# HF_AMP.net
KiCad netlist of a schematic drawn in Altium Designer
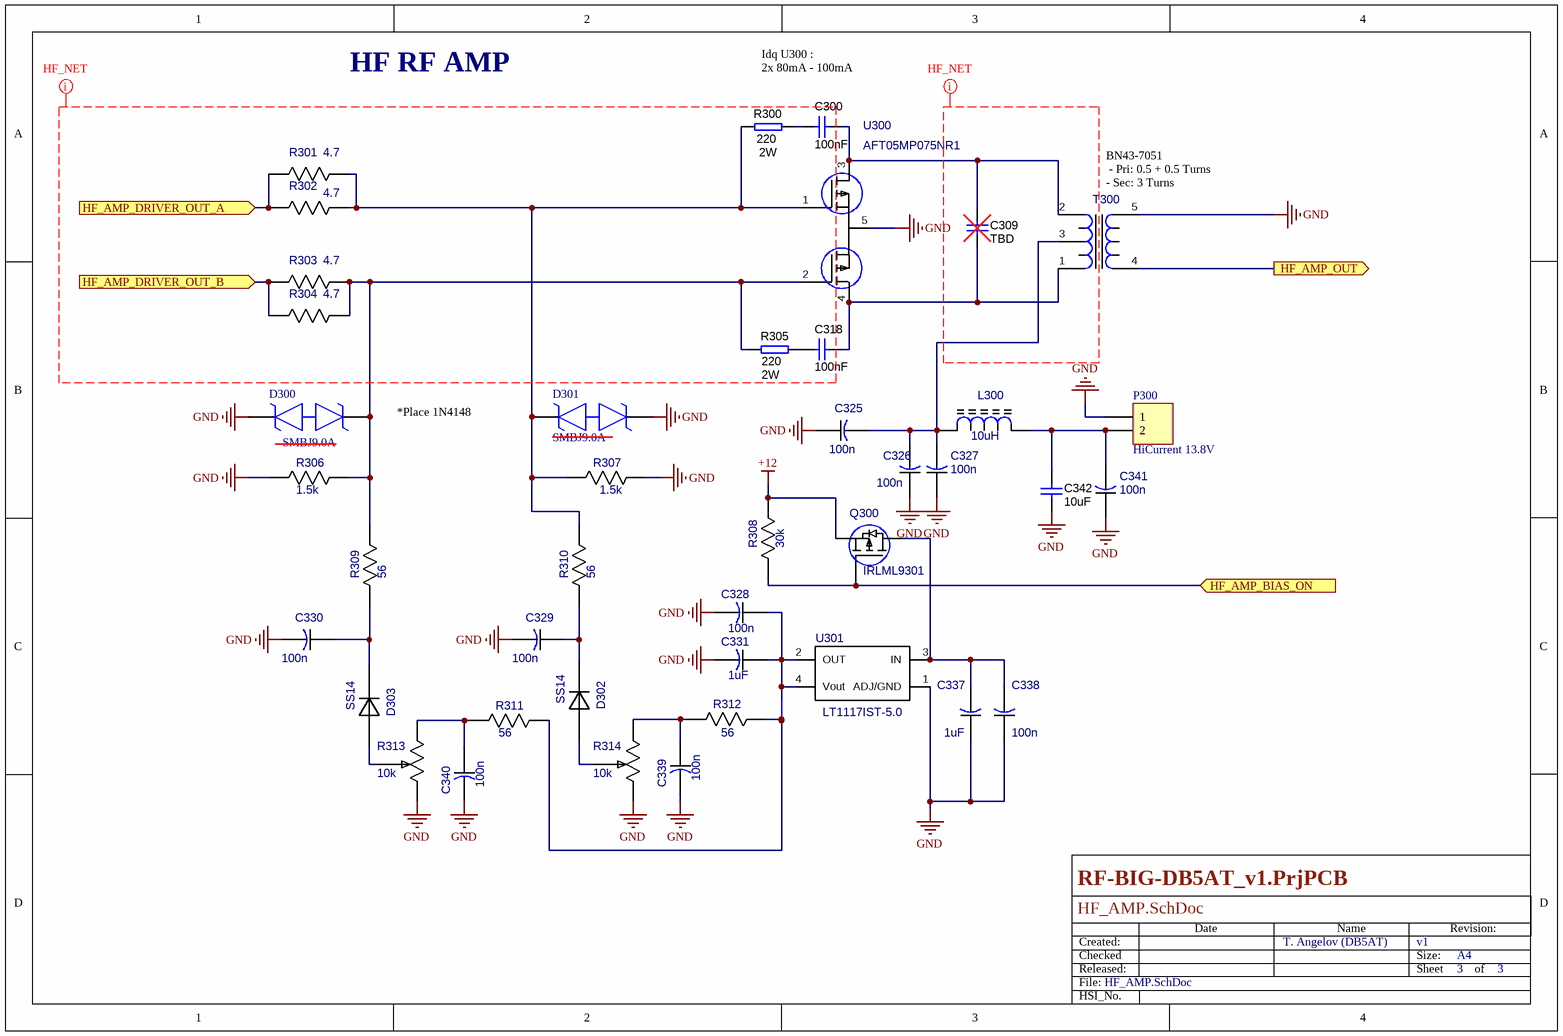
[diagram p0: HF_AMP.SchDoc]

(export (version "E")
  (design (tool "Eeschema 10.0.6"))
  (components
    (comp (ref "C300")
      (value "100nF")
      (footprint "1206_180")
      (description "CAP, CERM, +/- 10%, X7R, 1206")
      (libsource (lib "PSFB_v1") (part "C1206"))
    )
    (comp (ref "C309")
      (value "TBD")
      (footprint "1206_180")
      (description "CAP, CERM, +/- 10%, X7R, 1206")
      (libsource (lib "PSFB_v1") (part "C1206"))
    )
    (comp (ref "C318")
      (value "100nF")
      (footprint "1206_180")
      (description "CAP, CERM, +/- 10%, X7R, 1206")
      (libsource (lib "PSFB_v1") (part "C1206"))
    )
    (comp (ref "C325")
      (value "100n")
      (footprint "CAP_1206")
      (description "CAP_1206")
      (libsource (lib "*") (part "CAP_1206"))
    )
    (comp (ref "C326")
      (value "100n")
      (footprint "CAP_1206")
      (description "CAP_1206")
      (libsource (lib "*") (part "CAP_1206"))
    )
    (comp (ref "C327")
      (value "100n")
      (footprint "CAP_1206")
      (description "CAP_1206")
      (libsource (lib "*") (part "CAP_1206"))
    )
    (comp (ref "C328")
      (value "100n")
      (footprint "CAP_0805")
      (description "CAP_0805")
      (libsource (lib "*") (part "CAP_0805"))
    )
    (comp (ref "C329")
      (value "100n")
      (footprint "CAP_0805")
      (description "CAP_0805")
      (libsource (lib "*") (part "CAP_0805"))
    )
    (comp (ref "C330")
      (value "100n")
      (footprint "CAP_0805")
      (description "CAP_0805")
      (libsource (lib "*") (part "CAP_0805"))
    )
    (comp (ref "C331")
      (value "1uF")
      (footprint "CAP_0805")
      (description "CAP_0805")
      (libsource (lib "*") (part "CAP_0805"))
    )
    (comp (ref "C337")
      (value "1uF")
      (footprint "CAP_0805")
      (description "CAP_0805")
      (libsource (lib "*") (part "CAP_0805"))
    )
    (comp (ref "C338")
      (value "100n")
      (footprint "CAP_0805")
      (description "CAP_0805")
      (libsource (lib "*") (part "CAP_0805"))
    )
    (comp (ref "C339")
      (value "100n")
      (footprint "CAP_0805")
      (description "CAP_0805")
      (libsource (lib "*") (part "CAP_0805"))
    )
    (comp (ref "C340")
      (value "100n")
      (footprint "CAP_0805")
      (description "CAP_0805")
      (libsource (lib "*") (part "CAP_0805"))
    )
    (comp (ref "C341")
      (value "100n")
      (footprint "CAP_0805")
      (description "CAP_1206")
      (libsource (lib "*") (part "CAP_1206"))
    )
    (comp (ref "C342")
      (value "10uF")
      (footprint "1206_180")
      (description "CAP, CERM, +/- 10%, X7R, 1206")
      (libsource (lib "PSFB_v1") (part "C1206"))
    )
    (comp (ref "D300")
      (value "SMBJ9.0A")
      (footprint "SMBJ36CATR")
      (description "TVS Diode (Bi-directional)")
      (fields
        (field (name "MANUFACTURER_PART_NUMBER") "SMBJ16CA")
        (field (name "MOUSER PART NUMBER") "652-SMBJ16CA")
      )
      (libsource (lib "*") (part "SMBJ16CA"))
    )
    (comp (ref "D301")
      (value "SMBJ9.0A")
      (footprint "SMBJ36CATR")
      (description "TVS Diode (Bi-directional)")
      (fields
        (field (name "MANUFACTURER_PART_NUMBER") "SMBJ16CA")
        (field (name "MOUSER PART NUMBER") "652-SMBJ16CA")
      )
      (libsource (lib "*") (part "SMBJ16CA"))
    )
    (comp (ref "D302") (value "SS14") (footprint "SS14") (libsource (lib "*") (part "SS14")))
    (comp (ref "D303") (value "SS14") (footprint "SS14") (libsource (lib "*") (part "SS14")))
    (comp (ref "L300")
      (value "10uH")
      (footprint "IND_FERRITE_CORE")
      (description "Inductor")
      (libsource (lib "*") (part "IND_FERRITE_CORE"))
    )
    (comp (ref "P300")
      (value "HiCurrent 13.8V")
      (footprint "2 Pole Screw")
      (description "Header, 2-Pin")
      (fields (field (name "PUBLISHER") "Altium Limited"))
      (libsource (lib "Miscellaneous Connectors") (part "Header 2"))
    )
    (comp (ref "Q300")
      (value "IRLML9301")
      (footprint "SOT23")
      (description "MOSFET")
      (libsource (lib "*") (part "MOSFET_ENH_PD"))
    )
    (comp (ref "R300")
      (value "220")
      (footprint "Res_2W")
      (description "RES")
      (fields (field (name "VALUE2") "2W"))
      (libsource (lib "PSFB_v1") (part "R1206"))
    )
    (comp (ref "R301")
      (value "4.7")
      (footprint "RES_1206")
      (description "RES_1206")
      (libsource (lib "*") (part "RES_1206"))
    )
    (comp (ref "R302")
      (value "4.7")
      (footprint "RES_1206")
      (description "RES_1206")
      (libsource (lib "*") (part "RES_1206"))
    )
    (comp (ref "R303")
      (value "4.7")
      (footprint "RES_1206")
      (description "RES_1206")
      (libsource (lib "*") (part "RES_1206"))
    )
    (comp (ref "R304")
      (value "4.7")
      (footprint "RES_1206")
      (description "RES_1206")
      (libsource (lib "*") (part "RES_1206"))
    )
    (comp (ref "R305")
      (value "220")
      (footprint "Res_2W")
      (description "RES")
      (fields (field (name "VALUE2") "2W"))
      (libsource (lib "PSFB_v1") (part "R1206"))
    )
    (comp (ref "R306")
      (value "1.5k")
      (footprint "RES_0805")
      (description "RES_0805")
      (libsource (lib "*") (part "RES_0805"))
    )
    (comp (ref "R307")
      (value "1.5k")
      (footprint "RES_0805")
      (description "RES_0805")
      (libsource (lib "*") (part "RES_0805"))
    )
    (comp (ref "R308")
      (value "30k")
      (footprint "RES_0805")
      (description "RES_0805")
      (libsource (lib "*") (part "RES_0805"))
    )
    (comp (ref "R309")
      (value "56")
      (footprint "RES_0805")
      (description "RES_0805")
      (libsource (lib "*") (part "RES_0805"))
    )
    (comp (ref "R310")
      (value "56")
      (footprint "RES_0805")
      (description "RES_0805")
      (libsource (lib "*") (part "RES_0805"))
    )
    (comp (ref "R311")
      (value "56")
      (footprint "RES_0805")
      (description "RES_0805")
      (libsource (lib "*") (part "RES_0805"))
    )
    (comp (ref "R312")
      (value "56")
      (footprint "RES_0805")
      (description "RES_0805")
      (libsource (lib "*") (part "RES_0805"))
    )
    (comp (ref "R313")
      (value "10k")
      (footprint "3296W-1")
      (description "3296W-1-103LF")
      (fields (field (name "Comment") "ADJ-10k"))
      (libsource (lib "*") (part "306J"))
    )
    (comp (ref "R314")
      (value "10k")
      (footprint "3296W-1")
      (description "3296W-1-103LF")
      (fields (field (name "Comment") "ADJ-10k"))
      (libsource (lib "*") (part "306J"))
    )
    (comp (ref "T300")
      (value "TRANSF_HF2")
      (footprint "TRANSF_HF3 - bn43-7051")
      (libsource (lib "RF-UNIT-BIG") (part "TRANSF_RF2"))
    )
    (comp (ref "U300")
      (value "AFT05MP075NR1")
      (footprint "AFT05MP075NR1-Direct_Mount")
      (libsource (lib "RF-UNIT-BIG") (part "AFT05MP075NR1"))
    )
    (comp (ref "U301")
      (value "LT1117IST-5.0")
      (footprint "LT1117IST-ADJ")
      (libsource (lib "*") (part "LT1117IST-ADJ"))
    )
  )
  (nets
    (net (code "1") (name "+12") (class "Default")
      (node (ref "Q300") (pin "2") (pinfunction "S_2") (pintype "passive"))
      (node (ref "R308") (pin "2") (pinfunction "2_2") (pintype "passive"))
    )
    (net (code "2") (name "/HF_AMP_BIAS_ON") (class "Default")
      (node (ref "Q300") (pin "1") (pinfunction "G_1") (pintype "passive"))
      (node (ref "R308") (pin "1") (pinfunction "1_1") (pintype "passive"))
    )
    (net (code "3") (name "/HF_AMP_DRIVER_OUT_A") (class "Default")
      (node (ref "R301") (pin "1") (pinfunction "1_1") (pintype "passive"))
      (node (ref "R302") (pin "1") (pinfunction "1_1") (pintype "passive"))
    )
    (net (code "4") (name "/HF_AMP_DRIVER_OUT_B") (class "Default")
      (node (ref "R303") (pin "1") (pinfunction "1_1") (pintype "passive"))
      (node (ref "R304") (pin "1") (pinfunction "1_1") (pintype "passive"))
    )
    (net (code "5") (name "/HF_AMP_OUT") (class "Default")
      (node (ref "T300") (pin "4") (pinfunction "S1_4") (pintype "passive"))
    )
    (net (code "6") (name "GND") (class "Default")
      (node (ref "C325") (pin "1") (pinfunction "1_1") (pintype "passive"))
      (node (ref "C326") (pin "1") (pinfunction "1_1") (pintype "passive"))
      (node (ref "C327") (pin "1") (pinfunction "1_1") (pintype "passive"))
      (node (ref "C328") (pin "2") (pinfunction "2_2") (pintype "passive"))
      (node (ref "C329") (pin "2") (pinfunction "2_2") (pintype "passive"))
      (node (ref "C330") (pin "2") (pinfunction "2_2") (pintype "passive"))
      (node (ref "C331") (pin "2") (pinfunction "2_2") (pintype "passive"))
      (node (ref "C337") (pin "1") (pinfunction "1_1") (pintype "passive"))
      (node (ref "C338") (pin "1") (pinfunction "1_1") (pintype "passive"))
      (node (ref "C339") (pin "2") (pinfunction "2_2") (pintype "passive"))
      (node (ref "C340") (pin "2") (pinfunction "2_2") (pintype "passive"))
      (node (ref "C341") (pin "1") (pinfunction "1_1") (pintype "passive"))
      (node (ref "C342") (pin "1") (pinfunction "1_1") (pintype "passive"))
      (node (ref "D300") (pin "1") (pinfunction "1_1") (pintype "passive"))
      (node (ref "D301") (pin "1") (pinfunction "1_1") (pintype "passive"))
      (node (ref "P300") (pin "1") (pinfunction "1_1") (pintype "passive"))
      (node (ref "R306") (pin "1") (pinfunction "1_1") (pintype "passive"))
      (node (ref "R307") (pin "2") (pinfunction "2_2") (pintype "passive"))
      (node (ref "R313") (pin "1") (pinfunction "CCW_1") (pintype "passive"))
      (node (ref "R314") (pin "1") (pinfunction "CCW_1") (pintype "passive"))
      (node (ref "T300") (pin "5") (pinfunction "S2_5") (pintype "passive"))
      (node (ref "U300") (pin "5") (pinfunction "D1_5") (pintype "passive"))
      (node (ref "U301") (pin "1") (pinfunction "ADJ/GND_1") (pintype "passive"))
    )
    (net (code "7") (name "Net-(C300-Pad1)") (class "Default")
      (node (ref "C300") (pin "1") (pinfunction "1_1") (pintype "passive"))
      (node (ref "R300") (pin "2") (pinfunction "2_2") (pintype "passive"))
    )
    (net (code "8") (name "Net-(C318-Pad2)") (class "Default")
      (node (ref "C318") (pin "2") (pinfunction "2_2") (pintype "passive"))
      (node (ref "R305") (pin "1") (pinfunction "1_1") (pintype "passive"))
    )
    (net (code "9") (name "Net-(D302-A)") (class "Default")
      (node (ref "D302") (pin "2") (pinfunction "A_2") (pintype "passive"))
      (node (ref "R314") (pin "2") (pinfunction "W_2") (pintype "passive"))
    )
    (net (code "10") (name "Net-(D302-K)") (class "Default")
      (node (ref "C329") (pin "1") (pinfunction "1_1") (pintype "passive"))
      (node (ref "D302") (pin "1") (pinfunction "K_1") (pintype "passive"))
      (node (ref "R310") (pin "1") (pinfunction "1_1") (pintype "passive"))
    )
    (net (code "11") (name "Net-(D303-A)") (class "Default")
      (node (ref "D303") (pin "2") (pinfunction "A_2") (pintype "passive"))
      (node (ref "R313") (pin "2") (pinfunction "W_2") (pintype "passive"))
    )
    (net (code "12") (name "Net-(D303-K)") (class "Default")
      (node (ref "C330") (pin "1") (pinfunction "1_1") (pintype "passive"))
      (node (ref "D303") (pin "1") (pinfunction "K_1") (pintype "passive"))
      (node (ref "R309") (pin "1") (pinfunction "1_1") (pintype "passive"))
    )
    (net (code "13") (name "Net-(L300-A)") (class "Default")
      (node (ref "C325") (pin "2") (pinfunction "2_2") (pintype "passive"))
      (node (ref "C326") (pin "2") (pinfunction "2_2") (pintype "passive"))
      (node (ref "C327") (pin "2") (pinfunction "2_2") (pintype "passive"))
      (node (ref "L300") (pin "1") (pinfunction "A_1") (pintype "passive"))
      (node (ref "T300") (pin "3") (pinfunction "P3_3") (pintype "passive"))
    )
    (net (code "14") (name "Net-(L300-B)") (class "Default")
      (node (ref "C341") (pin "2") (pinfunction "2_2") (pintype "passive"))
      (node (ref "C342") (pin "2") (pinfunction "2_2") (pintype "passive"))
      (node (ref "L300") (pin "2") (pinfunction "B_2") (pintype "passive"))
      (node (ref "P300") (pin "2") (pinfunction "2_2") (pintype "passive"))
    )
    (net (code "15") (name "Net-(Q300-D)") (class "Default")
      (node (ref "C337") (pin "2") (pinfunction "2_2") (pintype "passive"))
      (node (ref "C338") (pin "2") (pinfunction "2_2") (pintype "passive"))
      (node (ref "Q300") (pin "3") (pinfunction "D_3") (pintype "passive"))
      (node (ref "U301") (pin "3") (pinfunction "IN_3") (pintype "passive"))
    )
    (net (code "16") (name "Net-(R313-CW)") (class "Default")
      (node (ref "C340") (pin "1") (pinfunction "1_1") (pintype "passive"))
      (node (ref "R311") (pin "1") (pinfunction "1_1") (pintype "passive"))
      (node (ref "R313") (pin "3") (pinfunction "CW_3") (pintype "passive"))
    )
    (net (code "17") (name "Net-(R314-CW)") (class "Default")
      (node (ref "C339") (pin "1") (pinfunction "1_1") (pintype "passive"))
      (node (ref "R312") (pin "1") (pinfunction "1_1") (pintype "passive"))
      (node (ref "R314") (pin "3") (pinfunction "CW_3") (pintype "passive"))
    )
    (net (code "18") (name "Net-(T300-P1)") (class "Default")
      (node (ref "C309") (pin "1") (pinfunction "1_1") (pintype "passive"))
      (node (ref "C318") (pin "1") (pinfunction "1_1") (pintype "passive"))
      (node (ref "T300") (pin "1") (pinfunction "P1_1") (pintype "passive"))
      (node (ref "U300") (pin "4") (pinfunction "D2_4") (pintype "passive"))
    )
    (net (code "19") (name "Net-(T300-P2)") (class "Default")
      (node (ref "C300") (pin "2") (pinfunction "2_2") (pintype "passive"))
      (node (ref "C309") (pin "2") (pinfunction "2_2") (pintype "passive"))
      (node (ref "T300") (pin "2") (pinfunction "P2_2") (pintype "passive"))
      (node (ref "U300") (pin "3") (pinfunction "D1_3") (pintype "passive"))
    )
    (net (code "20") (name "Net-(U300-G1)") (class "Default")
      (node (ref "D301") (pin "2") (pinfunction "2_2") (pintype "passive"))
      (node (ref "R300") (pin "1") (pinfunction "1_1") (pintype "passive"))
      (node (ref "R301") (pin "2") (pinfunction "2_2") (pintype "passive"))
      (node (ref "R302") (pin "2") (pinfunction "2_2") (pintype "passive"))
      (node (ref "R307") (pin "1") (pinfunction "1_1") (pintype "passive"))
      (node (ref "R310") (pin "2") (pinfunction "2_2") (pintype "passive"))
      (node (ref "U300") (pin "1") (pinfunction "G1_1") (pintype "passive"))
    )
    (net (code "21") (name "Net-(U300-G2)") (class "Default")
      (node (ref "D300") (pin "2") (pinfunction "2_2") (pintype "passive"))
      (node (ref "R303") (pin "2") (pinfunction "2_2") (pintype "passive"))
      (node (ref "R304") (pin "2") (pinfunction "2_2") (pintype "passive"))
      (node (ref "R305") (pin "2") (pinfunction "2_2") (pintype "passive"))
      (node (ref "R306") (pin "2") (pinfunction "2_2") (pintype "passive"))
      (node (ref "R309") (pin "2") (pinfunction "2_2") (pintype "passive"))
      (node (ref "U300") (pin "2") (pinfunction "G2_2") (pintype "passive"))
    )
    (net (code "22") (name "Net-(U301-OUT)") (class "Default")
      (node (ref "C328") (pin "1") (pinfunction "1_1") (pintype "passive"))
      (node (ref "C331") (pin "1") (pinfunction "1_1") (pintype "passive"))
      (node (ref "R311") (pin "2") (pinfunction "2_2") (pintype "passive"))
      (node (ref "R312") (pin "2") (pinfunction "2_2") (pintype "passive"))
      (node (ref "U301") (pin "2") (pinfunction "OUT_2") (pintype "passive"))
      (node (ref "U301") (pin "4") (pinfunction "Vout_4") (pintype "passive"))
    )
  )
)
